# charge_mode_preamplifier.net
KiCad netlist of a schematic drawn in Altium Designer
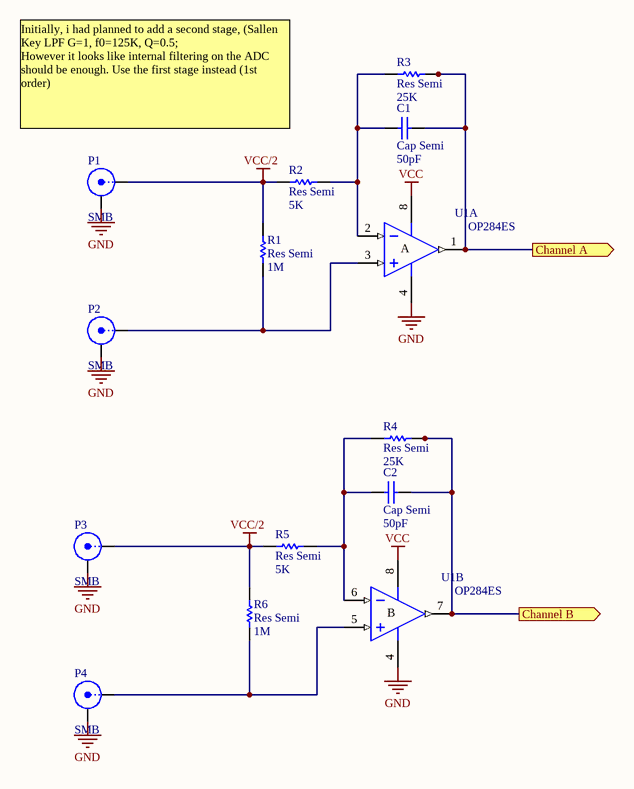
[diagram p0: charge_mode_preamplifier.SchDoc]

(export (version "E")
  (design (tool "Eeschema 10.0.6"))
  (components
    (comp (ref "C1")
      (value "Cap Semi")
      (footprint "CAPC1005L")
      (description "Capacitor (Semiconductor SIM Model)")
      (fields (field (name "ALTIUM_VALUE") "50pF") (field (name "PUBLISHER") "Altium Limited"))
      (libsource (lib "Miscellaneous Devices") (part "Cap Semi"))
    )
    (comp (ref "C2")
      (value "Cap Semi")
      (footprint "CAPC1005L")
      (description "Capacitor (Semiconductor SIM Model)")
      (fields (field (name "ALTIUM_VALUE") "50pF") (field (name "PUBLISHER") "Altium Limited"))
      (libsource (lib "Miscellaneous Devices") (part "Cap Semi"))
    )
    (comp (ref "P1")
      (value "SMB")
      (footprint "SMB_V-RJ45")
      (description "SMB Straight Connector")
      (fields (field (name "PUBLISHER") "Altium Limited"))
      (libsource (lib "Miscellaneous Connectors") (part "SMB"))
    )
    (comp (ref "P2")
      (value "SMB")
      (footprint "SMB_V-RJ45")
      (description "SMB Straight Connector")
      (fields (field (name "PUBLISHER") "Altium Limited"))
      (libsource (lib "Miscellaneous Connectors") (part "SMB"))
    )
    (comp (ref "P3")
      (value "SMB")
      (footprint "SMB_V-RJ45")
      (description "SMB Straight Connector")
      (fields (field (name "PUBLISHER") "Altium Limited"))
      (libsource (lib "Miscellaneous Connectors") (part "SMB"))
    )
    (comp (ref "P4")
      (value "SMB")
      (footprint "SMB_V-RJ45")
      (description "SMB Straight Connector")
      (fields (field (name "PUBLISHER") "Altium Limited"))
      (libsource (lib "Miscellaneous Connectors") (part "SMB"))
    )
    (comp (ref "R1")
      (value "Res Semi")
      (footprint "RESC1005L")
      (description "Semiconductor Resistor")
      (fields (field (name "ALTIUM_VALUE") "1M") (field (name "PUBLISHER") "Altium Limited"))
      (libsource (lib "Miscellaneous Devices") (part "Res Semi"))
    )
    (comp (ref "R2")
      (value "Res Semi")
      (footprint "RESC1005L")
      (description "Semiconductor Resistor")
      (fields (field (name "ALTIUM_VALUE") "5K") (field (name "PUBLISHER") "Altium Limited"))
      (libsource (lib "Miscellaneous Devices") (part "Res Semi"))
    )
    (comp (ref "R3")
      (value "Res Semi")
      (footprint "RESC1005L")
      (description "Semiconductor Resistor")
      (fields (field (name "ALTIUM_VALUE") "25K") (field (name "PUBLISHER") "Altium Limited"))
      (libsource (lib "Miscellaneous Devices") (part "Res Semi"))
    )
    (comp (ref "R4")
      (value "Res Semi")
      (footprint "RESC1005L")
      (description "Semiconductor Resistor")
      (fields (field (name "ALTIUM_VALUE") "25K") (field (name "PUBLISHER") "Altium Limited"))
      (libsource (lib "Miscellaneous Devices") (part "Res Semi"))
    )
    (comp (ref "R5")
      (value "Res Semi")
      (footprint "RESC1005L")
      (description "Semiconductor Resistor")
      (fields (field (name "ALTIUM_VALUE") "5K") (field (name "PUBLISHER") "Altium Limited"))
      (libsource (lib "Miscellaneous Devices") (part "Res Semi"))
    )
    (comp (ref "R6")
      (value "Res Semi")
      (footprint "RESC1005L")
      (description "Semiconductor Resistor")
      (fields (field (name "ALTIUM_VALUE") "1M") (field (name "PUBLISHER") "Altium Limited"))
      (libsource (lib "Miscellaneous Devices") (part "Res Semi"))
    )
    (comp (ref "U1")
      (value "OP284ES")
      (footprint "SO-8_N")
      (description "Precision Rail-to-Rail Input and Output Operational Amplifier")
      (fields (field (name "PUBLISHER") "Altium Limited"))
      (libsource (lib "AD Operational Amplifier") (part "OP284ES"))
    )
  )
  (nets
    (net (code "1") (name "/Channel A") (class "Default")
      (node (ref "C1") (pin "2") (pinfunction "2_2") (pintype "passive"))
      (node (ref "R3") (pin "2") (pinfunction "2_2") (pintype "passive"))
      (node (ref "U1") (pin "1") (pinfunction "OUT_1") (pintype "output"))
    )
    (net (code "2") (name "/Channel B") (class "Default")
      (node (ref "C2") (pin "2") (pinfunction "2_2") (pintype "passive"))
      (node (ref "R4") (pin "2") (pinfunction "2_2") (pintype "passive"))
      (node (ref "U1") (pin "7") (pinfunction "OUT_7") (pintype "output"))
    )
    (net (code "3") (name "GND") (class "Default")
      (node (ref "P1") (pin "2") (pinfunction "Y_2") (pintype "passive"))
      (node (ref "P2") (pin "2") (pinfunction "Y_2") (pintype "passive"))
      (node (ref "P3") (pin "2") (pinfunction "Y_2") (pintype "passive"))
      (node (ref "P4") (pin "2") (pinfunction "Y_2") (pintype "passive"))
      (node (ref "U1") (pin "4") (pinfunction "V-_4") (pintype "power_in"))
    )
    (net (code "4") (name "Net-(P2-X)") (class "Default")
      (node (ref "P2") (pin "1") (pinfunction "X_1") (pintype "passive"))
      (node (ref "R1") (pin "1") (pinfunction "1_1") (pintype "passive"))
      (node (ref "U1") (pin "3") (pinfunction "IN+_3") (pintype "input"))
    )
    (net (code "5") (name "Net-(P4-X)") (class "Default")
      (node (ref "P4") (pin "1") (pinfunction "X_1") (pintype "passive"))
      (node (ref "R6") (pin "1") (pinfunction "1_1") (pintype "passive"))
      (node (ref "U1") (pin "5") (pinfunction "IN+_5") (pintype "input"))
    )
    (net (code "6") (name "Net-(U1A-IN-)") (class "Default")
      (node (ref "C1") (pin "1") (pinfunction "1_1") (pintype "passive"))
      (node (ref "R2") (pin "2") (pinfunction "2_2") (pintype "passive"))
      (node (ref "R3") (pin "1") (pinfunction "1_1") (pintype "passive"))
      (node (ref "U1") (pin "2") (pinfunction "IN-_2") (pintype "input"))
    )
    (net (code "7") (name "Net-(U1B-IN-)") (class "Default")
      (node (ref "C2") (pin "1") (pinfunction "1_1") (pintype "passive"))
      (node (ref "R4") (pin "1") (pinfunction "1_1") (pintype "passive"))
      (node (ref "R5") (pin "2") (pinfunction "2_2") (pintype "passive"))
      (node (ref "U1") (pin "6") (pinfunction "IN-_6") (pintype "input"))
    )
    (net (code "8") (name "VCC") (class "Default")
      (node (ref "U1") (pin "8") (pinfunction "V+_8") (pintype "power_in"))
    )
    (net (code "9") (name "VCC{slash}2") (class "Default")
      (node (ref "P1") (pin "1") (pinfunction "X_1") (pintype "passive"))
      (node (ref "P3") (pin "1") (pinfunction "X_1") (pintype "passive"))
      (node (ref "R1") (pin "2") (pinfunction "2_2") (pintype "passive"))
      (node (ref "R2") (pin "1") (pinfunction "1_1") (pintype "passive"))
      (node (ref "R5") (pin "1") (pinfunction "1_1") (pintype "passive"))
      (node (ref "R6") (pin "2") (pinfunction "2_2") (pintype "passive"))
    )
  )
)
